# VESC_KS75600_mos_driver_conn.net
KiCad netlist of a schematic drawn in Altium Designer
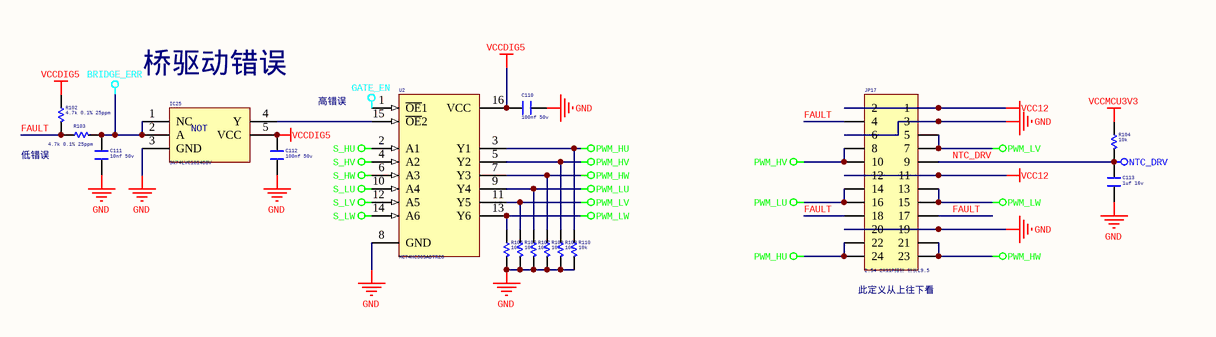
[diagram p0: VESC_KS75600_mos_driver_conn.SchDoc]

(export (version "E")
  (design (tool "Eeschema 10.0.6"))
  (components
    (comp (ref "C110")
      (value "100nf 50v")
      (footprint "C 0603")
      (description "无极性贴片电容")
      (fields (field (name "VOLTAGE") "50v"))
      (libsource (lib "电阻-电容-电感") (part "C"))
    )
    (comp (ref "C111")
      (value "10nf 50v")
      (footprint "C 0603")
      (description "无极性贴片电容")
      (fields (field (name "VOLTAGE") "50v"))
      (libsource (lib "电阻-电容-电感") (part "C"))
    )
    (comp (ref "C112")
      (value "100nf 50v")
      (footprint "C 0603")
      (description "无极性贴片电容")
      (fields (field (name "VOLTAGE") "50v"))
      (libsource (lib "电阻-电容-电感") (part "C"))
    )
    (comp (ref "C113")
      (value "1uf 16v")
      (footprint "C 0603")
      (description "无极性贴片电容")
      (fields (field (name "VOLTAGE") "16v"))
      (libsource (lib "电阻-电容-电感") (part "C"))
    )
    (comp (ref "IC25")
      (value "SN74LVC1G14DBV")
      (footprint "SOT23-5N")
      (description "单路施密特触发反向器")
      (libsource (lib "74系列芯片") (part "SN74LVC1G14"))
    )
    (comp (ref "JP17")
      (value "2.54 2X11P排针 针长L9.5")
      (footprint "HDR-12X2")
      (description "12*2P接插件")
      (libsource (lib "接插件") (part "Header 12X2"))
    )
    (comp (ref "R102")
      (value "4.7k 0.1% 25ppm")
      (footprint "R 0805")
      (description "贴片电阻")
      (libsource (lib "电阻-电容-电感") (part "R"))
    )
    (comp (ref "R103")
      (value "4.7k 0.1% 25ppm")
      (footprint "R 0805")
      (description "贴片电阻")
      (libsource (lib "电阻-电容-电感") (part "R"))
    )
    (comp (ref "R104")
      (value "10k")
      (footprint "R 0603")
      (description "贴片电阻")
      (libsource (lib "电阻-电容-电感") (part "R"))
    )
    (comp (ref "R105")
      (value "10k")
      (footprint "R 0805")
      (description "贴片电阻")
      (libsource (lib "电阻-电容-电感") (part "R"))
    )
    (comp (ref "R106")
      (value "10k")
      (footprint "R 0805")
      (description "贴片电阻")
      (libsource (lib "电阻-电容-电感") (part "R"))
    )
    (comp (ref "R107")
      (value "10k")
      (footprint "R 0805")
      (description "贴片电阻")
      (libsource (lib "电阻-电容-电感") (part "R"))
    )
    (comp (ref "R108")
      (value "10k")
      (footprint "R 0805")
      (description "贴片电阻")
      (libsource (lib "电阻-电容-电感") (part "R"))
    )
    (comp (ref "R109")
      (value "10k")
      (footprint "R 0805")
      (description "贴片电阻")
      (libsource (lib "电阻-电容-电感") (part "R"))
    )
    (comp (ref "R110")
      (value "10k")
      (footprint "R 0805")
      (description "贴片电阻")
      (libsource (lib "电阻-电容-电感") (part "R"))
    )
    (comp (ref "U2")
      (value "MC74HC365ADTR2G")
      (footprint "TSSOP16_L")
      (description "6路缓冲器")
      (libsource (lib "74系列芯片") (part "SN74HC365D"))
    )
  )
  (nets
    (net (code "1") (name "/FAULT") (class "Default")
      (node (ref "JP17") (pin "17") (pinfunction "17_17") (pintype "passive"))
      (node (ref "JP17") (pin "18") (pinfunction "18_18") (pintype "passive"))
      (node (ref "JP17") (pin "4") (pinfunction "4_4") (pintype "passive"))
      (node (ref "R102") (pin "2") (pinfunction "2_2") (pintype "passive"))
      (node (ref "R103") (pin "1") (pinfunction "1_1") (pintype "passive"))
    )
    (net (code "2") (name "BRIDGE_ERR") (class "Default")
      (node (ref "C111") (pin "1") (pinfunction "1_1") (pintype "passive"))
      (node (ref "IC25") (pin "1") (pinfunction "NC_1") (pintype "passive"))
      (node (ref "IC25") (pin "2") (pinfunction "A_2") (pintype "passive"))
      (node (ref "R103") (pin "2") (pinfunction "2_2") (pintype "passive"))
    )
    (net (code "3") (name "GATE_EN") (class "Default")
      (node (ref "U2") (pin "1") (pinfunction "~{OE}1_1") (pintype "input"))
    )
    (net (code "4") (name "GND") (class "Default")
      (node (ref "C110") (pin "2") (pinfunction "2_2") (pintype "passive"))
      (node (ref "C111") (pin "2") (pinfunction "2_2") (pintype "passive"))
      (node (ref "C112") (pin "1") (pinfunction "1_1") (pintype "passive"))
      (node (ref "C113") (pin "1") (pinfunction "1_1") (pintype "passive"))
      (node (ref "IC25") (pin "3") (pinfunction "GND_3") (pintype "passive"))
      (node (ref "JP17") (pin "19") (pinfunction "19_19") (pintype "passive"))
      (node (ref "JP17") (pin "20") (pinfunction "20_20") (pintype "passive"))
      (node (ref "JP17") (pin "3") (pinfunction "3_3") (pintype "passive"))
      (node (ref "JP17") (pin "6") (pinfunction "6_6") (pintype "passive"))
      (node (ref "R105") (pin "2") (pinfunction "2_2") (pintype "passive"))
      (node (ref "R106") (pin "2") (pinfunction "2_2") (pintype "passive"))
      (node (ref "R107") (pin "2") (pinfunction "2_2") (pintype "passive"))
      (node (ref "R108") (pin "2") (pinfunction "2_2") (pintype "passive"))
      (node (ref "R109") (pin "2") (pinfunction "2_2") (pintype "passive"))
      (node (ref "R110") (pin "2") (pinfunction "2_2") (pintype "passive"))
      (node (ref "U2") (pin "8") (pinfunction "GND_8") (pintype "power_in"))
    )
    (net (code "5") (name "NTC_DRV") (class "Default")
      (node (ref "C113") (pin "2") (pinfunction "2_2") (pintype "passive"))
      (node (ref "JP17") (pin "9") (pinfunction "9_9") (pintype "passive"))
      (node (ref "R104") (pin "2") (pinfunction "2_2") (pintype "passive"))
    )
    (net (code "6") (name "Net-(IC25-Y)") (class "Default")
      (node (ref "IC25") (pin "4") (pinfunction "Y_4") (pintype "passive"))
      (node (ref "U2") (pin "15") (pinfunction "~{OE}2_15") (pintype "input"))
    )
    (net (code "7") (name "PWM_HU") (class "Default")
      (node (ref "JP17") (pin "22") (pinfunction "22_22") (pintype "passive"))
      (node (ref "JP17") (pin "24") (pinfunction "24_24") (pintype "passive"))
      (node (ref "R110") (pin "1") (pinfunction "1_1") (pintype "passive"))
      (node (ref "U2") (pin "3") (pinfunction "Y1_3") (pintype "tri_state"))
    )
    (net (code "8") (name "PWM_HV") (class "Default")
      (node (ref "JP17") (pin "10") (pinfunction "10_10") (pintype "passive"))
      (node (ref "JP17") (pin "8") (pinfunction "8_8") (pintype "passive"))
      (node (ref "R109") (pin "1") (pinfunction "1_1") (pintype "passive"))
      (node (ref "U2") (pin "5") (pinfunction "Y2_5") (pintype "tri_state"))
    )
    (net (code "9") (name "PWM_HW") (class "Default")
      (node (ref "JP17") (pin "21") (pinfunction "21_21") (pintype "passive"))
      (node (ref "JP17") (pin "23") (pinfunction "23_23") (pintype "passive"))
      (node (ref "R108") (pin "1") (pinfunction "1_1") (pintype "passive"))
      (node (ref "U2") (pin "7") (pinfunction "Y3_7") (pintype "tri_state"))
    )
    (net (code "10") (name "PWM_LU") (class "Default")
      (node (ref "JP17") (pin "14") (pinfunction "14_14") (pintype "passive"))
      (node (ref "JP17") (pin "16") (pinfunction "16_16") (pintype "passive"))
      (node (ref "R107") (pin "1") (pinfunction "1_1") (pintype "passive"))
      (node (ref "U2") (pin "9") (pinfunction "Y4_9") (pintype "tri_state"))
    )
    (net (code "11") (name "PWM_LV") (class "Default")
      (node (ref "JP17") (pin "5") (pinfunction "5_5") (pintype "passive"))
      (node (ref "JP17") (pin "7") (pinfunction "7_7") (pintype "passive"))
      (node (ref "R106") (pin "1") (pinfunction "1_1") (pintype "passive"))
      (node (ref "U2") (pin "11") (pinfunction "Y5_11") (pintype "tri_state"))
    )
    (net (code "12") (name "PWM_LW") (class "Default")
      (node (ref "JP17") (pin "13") (pinfunction "13_13") (pintype "passive"))
      (node (ref "JP17") (pin "15") (pinfunction "15_15") (pintype "passive"))
      (node (ref "R105") (pin "1") (pinfunction "1_1") (pintype "passive"))
      (node (ref "U2") (pin "13") (pinfunction "Y6_13") (pintype "tri_state"))
    )
    (net (code "13") (name "S_HU") (class "Default")
      (node (ref "U2") (pin "2") (pinfunction "A1_2") (pintype "input"))
    )
    (net (code "14") (name "S_HV") (class "Default")
      (node (ref "U2") (pin "4") (pinfunction "A2_4") (pintype "input"))
    )
    (net (code "15") (name "S_HW") (class "Default")
      (node (ref "U2") (pin "6") (pinfunction "A3_6") (pintype "input"))
    )
    (net (code "16") (name "S_LU") (class "Default")
      (node (ref "U2") (pin "10") (pinfunction "A4_10") (pintype "input"))
    )
    (net (code "17") (name "S_LV") (class "Default")
      (node (ref "U2") (pin "12") (pinfunction "A5_12") (pintype "input"))
    )
    (net (code "18") (name "S_LW") (class "Default")
      (node (ref "U2") (pin "14") (pinfunction "A6_14") (pintype "input"))
    )
    (net (code "19") (name "VCC12") (class "Default")
      (node (ref "JP17") (pin "1") (pinfunction "1_1") (pintype "passive"))
      (node (ref "JP17") (pin "11") (pinfunction "11_11") (pintype "passive"))
      (node (ref "JP17") (pin "12") (pinfunction "12_12") (pintype "passive"))
      (node (ref "JP17") (pin "2") (pinfunction "2_2") (pintype "passive"))
    )
    (net (code "20") (name "VCCDIG5") (class "Default")
      (node (ref "C110") (pin "1") (pinfunction "1_1") (pintype "passive"))
      (node (ref "C112") (pin "2") (pinfunction "2_2") (pintype "passive"))
      (node (ref "IC25") (pin "5") (pinfunction "VCC_5") (pintype "passive"))
      (node (ref "R102") (pin "1") (pinfunction "1_1") (pintype "passive"))
      (node (ref "U2") (pin "16") (pinfunction "VCC_16") (pintype "power_in"))
    )
    (net (code "21") (name "VCCMCU3V3") (class "Default")
      (node (ref "R104") (pin "1") (pinfunction "1_1") (pintype "passive"))
    )
  )
)
